# ESP12_Adapter.net
KiCad netlist of a schematic drawn in EAGLE
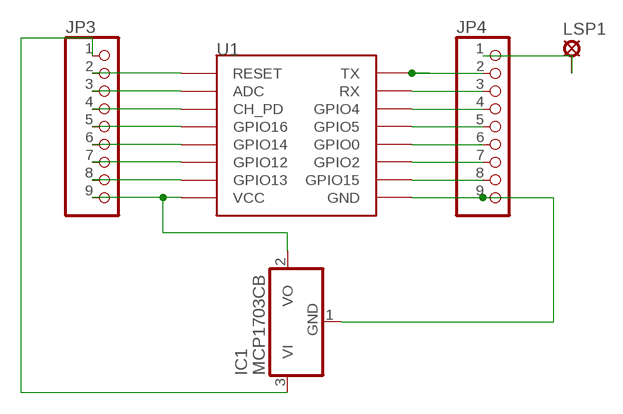
[diagram p0: schematic, sheet 1]

(export (version "E")
  (design (tool "Eeschema 10.0.6"))
  (components
    (comp (ref "IC1")
      (value "MCP1703CB")
      (footprint "eagle-import:SOT23")
      (libsource (lib "eagle-import") (part "MCP1703CB"))
    )
    (comp (ref "JP3")
      (value "PINHD-1X9")
      (footprint "eagle-import:1X09")
      (libsource (lib "eagle-import") (part "PINHD-1X9"))
    )
    (comp (ref "JP4")
      (value "PINHD-1X9")
      (footprint "eagle-import:1X09")
      (libsource (lib "eagle-import") (part "PINHD-1X9"))
    )
    (comp (ref "LSP1")
      (value "LSP10")
      (footprint "eagle-import:LSP10")
      (libsource (lib "eagle-import") (part "LSP10"))
    )
    (comp (ref "U1")
      (value "ESP12")
      (footprint "eagle-import:ESP12")
      (libsource (lib "eagle-import") (part "ESP12"))
    )
  )
  (nets
    (net (code "1") (name "Net-(IC1-GND)") (class "Default")
      (node (ref "IC1") (pin "1") (pinfunction "GND_1") (pintype "passive"))
      (node (ref "JP4") (pin "9") (pinfunction "9_9") (pintype "passive"))
      (node (ref "U1") (pin "GND") (pinfunction "GND_GND") (pintype "bidirectional"))
    )
    (net (code "2") (name "Net-(IC1-VI)") (class "Default")
      (node (ref "IC1") (pin "3") (pinfunction "VI_3") (pintype "input"))
      (node (ref "JP3") (pin "1") (pinfunction "1_1") (pintype "passive"))
    )
    (net (code "3") (name "Net-(IC1-VO)") (class "Default")
      (node (ref "IC1") (pin "2") (pinfunction "VO_2") (pintype "passive"))
      (node (ref "JP3") (pin "9") (pinfunction "9_9") (pintype "passive"))
      (node (ref "U1") (pin "VCC") (pinfunction "VCC_VCC") (pintype "bidirectional"))
    )
    (net (code "4") (name "Net-(JP3-Pad2)") (class "Default")
      (node (ref "JP3") (pin "2") (pinfunction "2_2") (pintype "passive"))
      (node (ref "U1") (pin "RESET") (pinfunction "RESET_RESET") (pintype "bidirectional"))
    )
    (net (code "5") (name "Net-(JP3-Pad3)") (class "Default")
      (node (ref "JP3") (pin "3") (pinfunction "3_3") (pintype "passive"))
      (node (ref "U1") (pin "ADC") (pinfunction "ADC_ADC") (pintype "bidirectional"))
    )
    (net (code "6") (name "Net-(JP3-Pad4)") (class "Default")
      (node (ref "JP3") (pin "4") (pinfunction "4_4") (pintype "passive"))
      (node (ref "U1") (pin "CH_PD") (pinfunction "CH_PD_CH_PD") (pintype "bidirectional"))
    )
    (net (code "7") (name "Net-(JP3-Pad5)") (class "Default")
      (node (ref "JP3") (pin "5") (pinfunction "5_5") (pintype "passive"))
      (node (ref "U1") (pin "GPIO16") (pinfunction "GPIO16_GPIO16") (pintype "bidirectional"))
    )
    (net (code "8") (name "Net-(JP3-Pad6)") (class "Default")
      (node (ref "JP3") (pin "6") (pinfunction "6_6") (pintype "passive"))
      (node (ref "U1") (pin "GPIO14") (pinfunction "GPIO14_GPIO14") (pintype "bidirectional"))
    )
    (net (code "9") (name "Net-(JP3-Pad7)") (class "Default")
      (node (ref "JP3") (pin "7") (pinfunction "7_7") (pintype "passive"))
      (node (ref "U1") (pin "GPIO12") (pinfunction "GPIO12_GPIO12") (pintype "bidirectional"))
    )
    (net (code "10") (name "Net-(JP3-Pad8)") (class "Default")
      (node (ref "JP3") (pin "8") (pinfunction "8_8") (pintype "passive"))
      (node (ref "U1") (pin "GPIO13") (pinfunction "GPIO13_GPIO13") (pintype "bidirectional"))
    )
    (net (code "11") (name "Net-(JP4-Pad1)") (class "Default")
      (node (ref "JP4") (pin "1") (pinfunction "1_1") (pintype "passive"))
      (node (ref "LSP1") (pin "MP") (pinfunction "MP_MP") (pintype "passive"))
    )
    (net (code "12") (name "Net-(JP4-Pad2)") (class "Default")
      (node (ref "JP4") (pin "2") (pinfunction "2_2") (pintype "passive"))
      (node (ref "U1") (pin "TX") (pinfunction "TX_TX") (pintype "bidirectional"))
    )
    (net (code "13") (name "Net-(JP4-Pad3)") (class "Default")
      (node (ref "JP4") (pin "3") (pinfunction "3_3") (pintype "passive"))
      (node (ref "U1") (pin "RX") (pinfunction "RX_RX") (pintype "bidirectional"))
    )
    (net (code "14") (name "Net-(JP4-Pad4)") (class "Default")
      (node (ref "JP4") (pin "4") (pinfunction "4_4") (pintype "passive"))
      (node (ref "U1") (pin "GPIO4") (pinfunction "GPIO4_GPIO4") (pintype "bidirectional"))
    )
    (net (code "15") (name "Net-(JP4-Pad5)") (class "Default")
      (node (ref "JP4") (pin "5") (pinfunction "5_5") (pintype "passive"))
      (node (ref "U1") (pin "GPIO5") (pinfunction "GPIO5_GPIO5") (pintype "bidirectional"))
    )
    (net (code "16") (name "Net-(JP4-Pad6)") (class "Default")
      (node (ref "JP4") (pin "6") (pinfunction "6_6") (pintype "passive"))
      (node (ref "U1") (pin "GPIO0") (pinfunction "GPIO0_GPIO0") (pintype "bidirectional"))
    )
    (net (code "17") (name "Net-(JP4-Pad7)") (class "Default")
      (node (ref "JP4") (pin "7") (pinfunction "7_7") (pintype "passive"))
      (node (ref "U1") (pin "GPIO2") (pinfunction "GPIO2_GPIO2") (pintype "bidirectional"))
    )
    (net (code "18") (name "Net-(JP4-Pad8)") (class "Default")
      (node (ref "JP4") (pin "8") (pinfunction "8_8") (pintype "passive"))
      (node (ref "U1") (pin "GPIO15") (pinfunction "GPIO15_GPIO15") (pintype "bidirectional"))
    )
  )
)
